# SH5_-_MICROCONTROLLER.net
KiCad netlist of a schematic drawn in Altium Designer
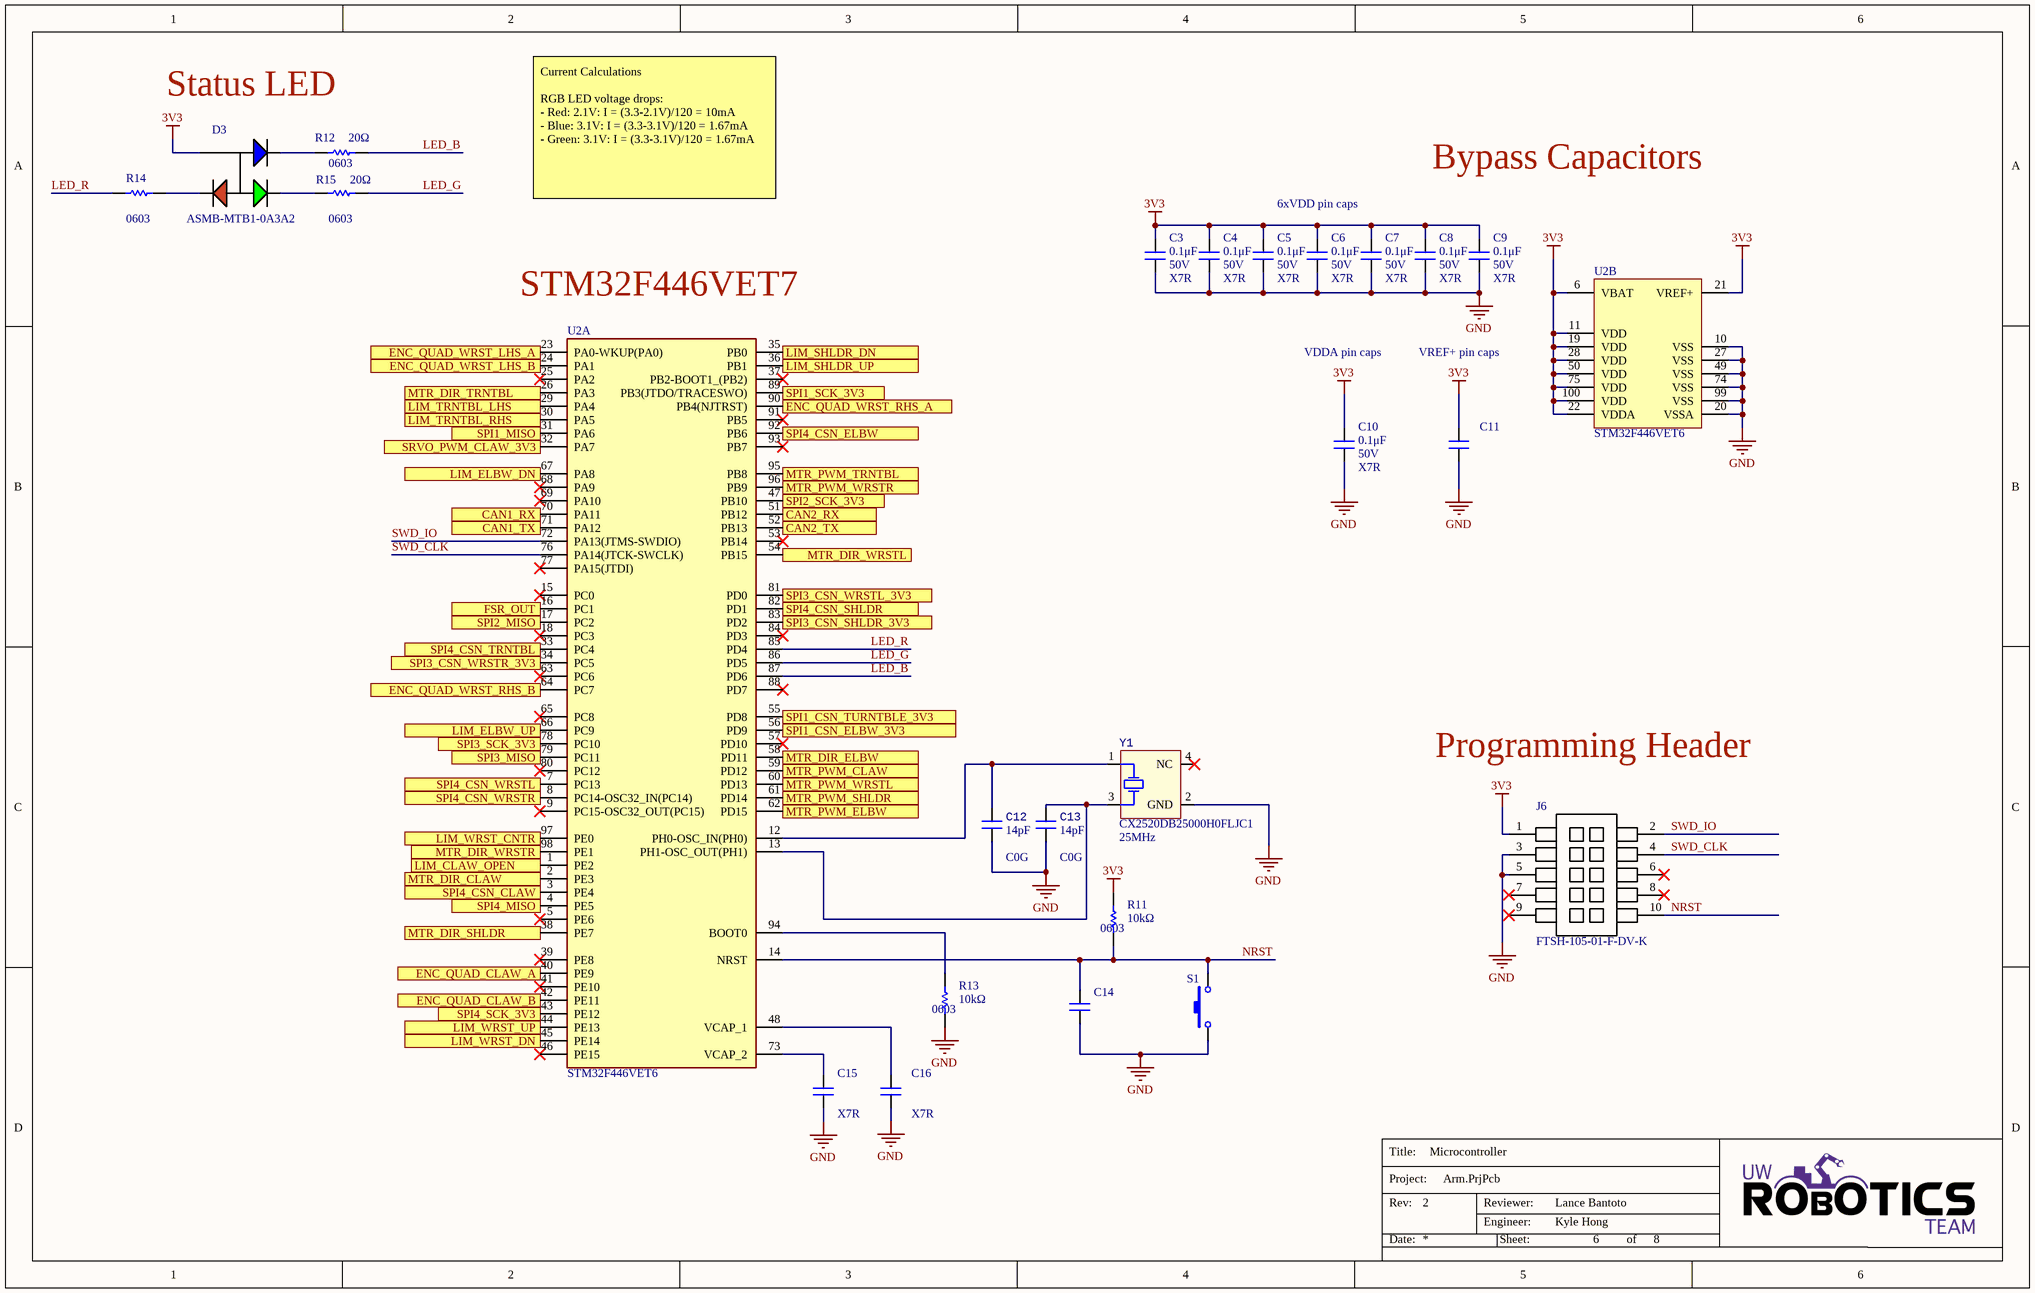
[diagram p0: SH5 - MICROCONTROLLER.SchDoc]

(export (version "E")
  (design (tool "Eeschema 10.0.6"))
  (components
    (comp (ref "C3")
      (value "0.1μF")
      (footprint "CAP0603")
      (description "CAP CER 0.1UF 50V X7R 0603")
      (fields
        (field (name "VOLTAGE RATING") "50V")
        (field (name "DIELECTRIC") "X7R")
        (field (name "Comment") "CAP_0.1uF_50V_0603")
      )
      (libsource (lib "UWRT_Schematic_Library_2020") (part "CAP_0.1uF_50V_0603"))
    )
    (comp (ref "C4")
      (value "0.1μF")
      (footprint "CAP0603")
      (description "CAP CER 0.1UF 50V X7R 0603")
      (fields
        (field (name "VOLTAGE RATING") "50V")
        (field (name "DIELECTRIC") "X7R")
        (field (name "Comment") "CAP_0.1uF_50V_0603")
      )
      (libsource (lib "UWRT_Schematic_Library_2020") (part "CAP_0.1uF_50V_0603"))
    )
    (comp (ref "C5")
      (value "0.1μF")
      (footprint "CAP0603")
      (description "CAP CER 0.1UF 50V X7R 0603")
      (fields
        (field (name "VOLTAGE RATING") "50V")
        (field (name "DIELECTRIC") "X7R")
        (field (name "Comment") "CAP_0.1uF_50V_0603")
      )
      (libsource (lib "UWRT_Schematic_Library_2020") (part "CAP_0.1uF_50V_0603"))
    )
    (comp (ref "C6")
      (value "0.1μF")
      (footprint "CAP0603")
      (description "CAP CER 0.1UF 50V X7R 0603")
      (fields
        (field (name "VOLTAGE RATING") "50V")
        (field (name "DIELECTRIC") "X7R")
        (field (name "Comment") "CAP_0.1uF_50V_0603")
      )
      (libsource (lib "UWRT_Schematic_Library_2020") (part "CAP_0.1uF_50V_0603"))
    )
    (comp (ref "C7")
      (value "0.1μF")
      (footprint "CAP0603")
      (description "CAP CER 0.1UF 50V X7R 0603")
      (fields
        (field (name "VOLTAGE RATING") "50V")
        (field (name "DIELECTRIC") "X7R")
        (field (name "Comment") "CAP_0.1uF_50V_0603")
      )
      (libsource (lib "UWRT_Schematic_Library_2020") (part "CAP_0.1uF_50V_0603"))
    )
    (comp (ref "C8")
      (value "0.1μF")
      (footprint "CAP0603")
      (description "CAP CER 0.1UF 50V X7R 0603")
      (fields
        (field (name "VOLTAGE RATING") "50V")
        (field (name "DIELECTRIC") "X7R")
        (field (name "Comment") "CAP_0.1uF_50V_0603")
      )
      (libsource (lib "UWRT_Schematic_Library_2020") (part "CAP_0.1uF_50V_0603"))
    )
    (comp (ref "C9")
      (value "0.1μF")
      (footprint "CAP0603")
      (description "CAP CER 0.1UF 50V X7R 0603")
      (fields
        (field (name "VOLTAGE RATING") "50V")
        (field (name "DIELECTRIC") "X7R")
        (field (name "Comment") "CAP_0.1uF_50V_0603")
      )
      (libsource (lib "UWRT_Schematic_Library_2020") (part "CAP_0.1uF_50V_0603"))
    )
    (comp (ref "C10")
      (value "0.1μF")
      (footprint "CAP0603")
      (description "CAP CER 0.1UF 50V X7R 0603")
      (fields
        (field (name "VOLTAGE RATING") "50V")
        (field (name "DIELECTRIC") "X7R")
        (field (name "Comment") "CAP_0.1uF_50V_0603")
      )
      (libsource (lib "UWRT_Schematic_Library_2020") (part "CAP_0.1uF_50V_0603"))
    )
    (comp (ref "C11")
      (value "CAP_1uF_25V_0603")
      (footprint "CAP0603")
      (description "CAP CER 1UF 25V X5R 0603")
      (libsource (lib "UWRT_Schematic_Library_2020") (part "CAP_1uF_25V_0603"))
    )
    (comp (ref "C12")
      (value "14pF")
      (footprint "CAP0603")
      (description "CAP CER 14PF 50V C0G/NP0 0603")
      (fields (field (name "DIELECTRIC") "C0G") (field (name "Comment") "CAP_14pF_50V_0603"))
      (libsource (lib "UWRT_Schematic_Library_2020") (part "CAP_14pF_50V_0603"))
    )
    (comp (ref "C13")
      (value "14pF")
      (footprint "CAP0603")
      (description "CAP CER 14PF 50V C0G/NP0 0603")
      (fields (field (name "DIELECTRIC") "C0G") (field (name "Comment") "CAP_14pF_50V_0603"))
      (libsource (lib "UWRT_Schematic_Library_2020") (part "CAP_14pF_50V_0603"))
    )
    (comp (ref "C14")
      (value "CAP_1uF_25V_0603")
      (footprint "CAP0603")
      (description "CAP CER 1UF 25V X5R 0603")
      (libsource (lib "UWRT_Schematic_Library_2020") (part "CAP_1uF_25V_0603"))
    )
    (comp (ref "C15")
      (value "CAP_4.7uF_50V_1206")
      (footprint "CAP1206")
      (description "CAP CER 4.7UF 50V X7R 1206")
      (fields (field (name "DIELECTRIC") "X7R"))
      (libsource (lib "UWRT_Schematic_Library_2020") (part "CAP_4.7uF_50V_1206"))
    )
    (comp (ref "C16")
      (value "CAP_4.7uF_50V_1206")
      (footprint "CAP1206")
      (description "CAP CER 4.7UF 50V X7R 1206")
      (fields (field (name "DIELECTRIC") "X7R"))
      (libsource (lib "UWRT_Schematic_Library_2020") (part "CAP_4.7uF_50V_1206"))
    )
    (comp (ref "D3")
      (value "LED_RGB")
      (footprint "LED_RGB")
      (description "LED RGB DIFFUSED 4PLCC SMD")
      (fields (field (name "MANUFACTURER PART NUMBER 1") "ASMB-MTB1-0A3A2"))
      (libsource (lib "UWRT_Schematic_Library_2020") (part "LED_RGB"))
    )
    (comp (ref "J6")
      (value "CON_PROGRAMMING")
      (footprint "FTSH-105-01-F-DV-K-P-TR")
      (description "CONN HEADER SMD 10POS 1.27MM")
      (fields (field (name "MANUFACTURER PART NUMBER 1") "FTSH-105-01-F-DV-K"))
      (libsource (lib "UWRT_Schematic_Library_2020") (part "CON_PROGRAMMING"))
    )
    (comp (ref "R11")
      (value "10kΩ")
      (footprint "RESC0603")
      (description "RES 10K OHM 5% 1/10W 0603")
      (fields (field (name "PACKAGE/FOOTPRINT") "0603") (field (name "Comment") "RES_10kΩ_0603_5%"))
      (libsource (lib "UWRT_Schematic_Library_2020") (part "RES_10kΩ_0603_5%"))
    )
    (comp (ref "R12")
      (value "20Ω")
      (footprint "RESC0603")
      (description "RES 20 OHM 5% 1/10W 0603")
      (fields (field (name "PACKAGE/FOOTPRINT") "0603") (field (name "Comment") "RES_20Ω_0603_5%"))
      (libsource (lib "UWRT_Schematic_Library_2020") (part "RES_20Ω_0603_5%"))
    )
    (comp (ref "R13")
      (value "10kΩ")
      (footprint "RESC0603")
      (description "RES 10K OHM 5% 1/10W 0603")
      (fields (field (name "PACKAGE/FOOTPRINT") "0603") (field (name "Comment") "RES_10kΩ_0603_5%"))
      (libsource (lib "UWRT_Schematic_Library_2020") (part "RES_10kΩ_0603_5%"))
    )
    (comp (ref "R14")
      (value "RES_120Ω_0603_5%_HP")
      (footprint "RESC0603")
      (description "RES 120 OHM 5% 1/4W 0603")
      (fields (field (name "PACKAGE/FOOTPRINT") "0603"))
      (libsource (lib "UWRT_Schematic_Library_2020") (part "RES_120Ω_0603_5%_HP"))
    )
    (comp (ref "R15")
      (value "20Ω")
      (footprint "RESC0603")
      (description "RES 20 OHM 5% 1/10W 0603")
      (fields (field (name "PACKAGE/FOOTPRINT") "0603") (field (name "Comment") "RES_20Ω_0603_5%"))
      (libsource (lib "UWRT_Schematic_Library_2020") (part "RES_20Ω_0603_5%"))
    )
    (comp (ref "S1")
      (value "SW_TACTILE")
      (footprint "B3U-1000P")
      (description "SWITCH TACTILE SPST-NO 0.05A 12V")
      (libsource (lib "UWRT_Schematic_Library_2020") (part "SW_TACTILE"))
    )
    (comp (ref "U2")
      (value "STM32F446VET6")
      (footprint "STM32F446VET6")
      (description "IC MCU 32BIT 512KB FLASH 100LQFP")
      (libsource (lib "UWRT_Schematic_Library_2020") (part "STM32F446VET6"))
    )
    (comp (ref "Y1")
      (value "CRYSTAL_25MHZ")
      (footprint "SOIC254P1016X440-4N")
      (description "CRYSTAL 25.0000MHZ 12PF SMD")
      (fields
        (field (name "MANUFACTURER PART NUMBER 1") "CX2520DB25000H0FLJC1")
        (field (name "FREQUENCY") "25MHz")
      )
      (libsource (lib "UWRT_Schematic_Library_2020") (part "CRYSTAL_25MHZ"))
    )
  )
  (nets
    (net (code "1") (name "/CAN1_RX") (class "Default")
      (node (ref "U2") (pin "70") (pinfunction "PA11_70") (pintype "passive"))
    )
    (net (code "2") (name "/CAN1_TX") (class "Default")
      (node (ref "U2") (pin "71") (pinfunction "PA12_71") (pintype "passive"))
    )
    (net (code "3") (name "/CAN2_RX") (class "Default")
      (node (ref "U2") (pin "51") (pinfunction "PB12_51") (pintype "passive"))
    )
    (net (code "4") (name "/CAN2_TX") (class "Default")
      (node (ref "U2") (pin "52") (pinfunction "PB13_52") (pintype "passive"))
    )
    (net (code "5") (name "/ENC_QUAD_CLAW_A") (class "Default")
      (node (ref "U2") (pin "40") (pinfunction "PE9_40") (pintype "passive"))
    )
    (net (code "6") (name "/ENC_QUAD_CLAW_B") (class "Default")
      (node (ref "U2") (pin "42") (pinfunction "PE11_42") (pintype "passive"))
    )
    (net (code "7") (name "/ENC_QUAD_WRST_LHS_A") (class "Default")
      (node (ref "U2") (pin "23") (pinfunction "PA0-WKUP(PA0)_23") (pintype "passive"))
    )
    (net (code "8") (name "/ENC_QUAD_WRST_LHS_B") (class "Default")
      (node (ref "U2") (pin "24") (pinfunction "PA1_24") (pintype "passive"))
    )
    (net (code "9") (name "/ENC_QUAD_WRST_RHS_A") (class "Default")
      (node (ref "U2") (pin "90") (pinfunction "PB4(NJTRST)_90") (pintype "passive"))
    )
    (net (code "10") (name "/ENC_QUAD_WRST_RHS_B") (class "Default")
      (node (ref "U2") (pin "64") (pinfunction "PC7_64") (pintype "passive"))
    )
    (net (code "11") (name "/FSR_OUT") (class "Default")
      (node (ref "U2") (pin "16") (pinfunction "PC1_16") (pintype "passive"))
    )
    (net (code "12") (name "/LED_B") (class "Default")
      (node (ref "R12") (pin "2") (pinfunction "2_2") (pintype "passive"))
      (node (ref "U2") (pin "87") (pinfunction "PD6_87") (pintype "passive"))
    )
    (net (code "13") (name "/LED_G") (class "Default")
      (node (ref "R15") (pin "2") (pinfunction "2_2") (pintype "passive"))
      (node (ref "U2") (pin "86") (pinfunction "PD5_86") (pintype "passive"))
    )
    (net (code "14") (name "/LED_R") (class "Default")
      (node (ref "R14") (pin "1") (pinfunction "1_1") (pintype "passive"))
      (node (ref "U2") (pin "85") (pinfunction "PD4_85") (pintype "passive"))
    )
    (net (code "15") (name "/LIM_CLAW_OPEN") (class "Default")
      (node (ref "U2") (pin "1") (pinfunction "PE2_1") (pintype "passive"))
    )
    (net (code "16") (name "/LIM_ELBW_DN") (class "Default")
      (node (ref "U2") (pin "67") (pinfunction "PA8_67") (pintype "passive"))
    )
    (net (code "17") (name "/LIM_ELBW_UP") (class "Default")
      (node (ref "U2") (pin "66") (pinfunction "PC9_66") (pintype "passive"))
    )
    (net (code "18") (name "/LIM_SHLDR_DN") (class "Default")
      (node (ref "U2") (pin "35") (pinfunction "PB0_35") (pintype "passive"))
    )
    (net (code "19") (name "/LIM_SHLDR_UP") (class "Default")
      (node (ref "U2") (pin "36") (pinfunction "PB1_36") (pintype "passive"))
    )
    (net (code "20") (name "/LIM_TRNTBL_LHS") (class "Default")
      (node (ref "U2") (pin "29") (pinfunction "PA4_29") (pintype "passive"))
    )
    (net (code "21") (name "/LIM_TRNTBL_RHS") (class "Default")
      (node (ref "U2") (pin "30") (pinfunction "PA5_30") (pintype "passive"))
    )
    (net (code "22") (name "/LIM_WRST_CNTR") (class "Default")
      (node (ref "U2") (pin "97") (pinfunction "PE0_97") (pintype "passive"))
    )
    (net (code "23") (name "/LIM_WRST_DN") (class "Default")
      (node (ref "U2") (pin "45") (pinfunction "PE14_45") (pintype "passive"))
    )
    (net (code "24") (name "/LIM_WRST_UP") (class "Default")
      (node (ref "U2") (pin "44") (pinfunction "PE13_44") (pintype "passive"))
    )
    (net (code "25") (name "/MTR_DIR_CLAW") (class "Default")
      (node (ref "U2") (pin "2") (pinfunction "PE3_2") (pintype "passive"))
    )
    (net (code "26") (name "/MTR_DIR_ELBW") (class "Default")
      (node (ref "U2") (pin "58") (pinfunction "PD11_58") (pintype "passive"))
    )
    (net (code "27") (name "/MTR_DIR_SHLDR") (class "Default")
      (node (ref "U2") (pin "38") (pinfunction "PE7_38") (pintype "passive"))
    )
    (net (code "28") (name "/MTR_DIR_TRNTBL") (class "Default")
      (node (ref "U2") (pin "26") (pinfunction "PA3_26") (pintype "passive"))
    )
    (net (code "29") (name "/MTR_DIR_WRSTL") (class "Default")
      (node (ref "U2") (pin "54") (pinfunction "PB15_54") (pintype "passive"))
    )
    (net (code "30") (name "/MTR_DIR_WRSTR") (class "Default")
      (node (ref "U2") (pin "98") (pinfunction "PE1_98") (pintype "passive"))
    )
    (net (code "31") (name "/MTR_PWM_CLAW") (class "Default")
      (node (ref "U2") (pin "59") (pinfunction "PD12_59") (pintype "passive"))
    )
    (net (code "32") (name "/MTR_PWM_ELBW") (class "Default")
      (node (ref "U2") (pin "62") (pinfunction "PD15_62") (pintype "passive"))
    )
    (net (code "33") (name "/MTR_PWM_SHLDR") (class "Default")
      (node (ref "U2") (pin "61") (pinfunction "PD14_61") (pintype "passive"))
    )
    (net (code "34") (name "/MTR_PWM_TRNTBL") (class "Default")
      (node (ref "U2") (pin "95") (pinfunction "PB8_95") (pintype "passive"))
    )
    (net (code "35") (name "/MTR_PWM_WRSTL") (class "Default")
      (node (ref "U2") (pin "60") (pinfunction "PD13_60") (pintype "passive"))
    )
    (net (code "36") (name "/MTR_PWM_WRSTR") (class "Default")
      (node (ref "U2") (pin "96") (pinfunction "PB9_96") (pintype "passive"))
    )
    (net (code "37") (name "/NRST") (class "Default")
      (node (ref "C14") (pin "2") (pinfunction "2_2") (pintype "passive"))
      (node (ref "J6") (pin "10") (pinfunction "10_10") (pintype "passive"))
      (node (ref "R11") (pin "2") (pinfunction "2_2") (pintype "passive"))
      (node (ref "S1") (pin "2") (pinfunction "2_2") (pintype "passive"))
      (node (ref "U2") (pin "14") (pinfunction "NRST_14") (pintype "passive"))
    )
    (net (code "38") (name "/SPI1_CSN_ELBW_3V3") (class "Default")
      (node (ref "U2") (pin "56") (pinfunction "PD9_56") (pintype "passive"))
    )
    (net (code "39") (name "/SPI1_CSN_TURNTBLE_3V3") (class "Default")
      (node (ref "U2") (pin "55") (pinfunction "PD8_55") (pintype "passive"))
    )
    (net (code "40") (name "/SPI1_MISO") (class "Default")
      (node (ref "U2") (pin "31") (pinfunction "PA6_31") (pintype "passive"))
    )
    (net (code "41") (name "/SPI1_SCK_3V3") (class "Default")
      (node (ref "U2") (pin "89") (pinfunction "PB3(JTDO/TRACESWO)_89") (pintype "passive"))
    )
    (net (code "42") (name "/SPI2_MISO") (class "Default")
      (node (ref "U2") (pin "17") (pinfunction "PC2_17") (pintype "passive"))
    )
    (net (code "43") (name "/SPI2_SCK_3V3") (class "Default")
      (node (ref "U2") (pin "47") (pinfunction "PB10_47") (pintype "passive"))
    )
    (net (code "44") (name "/SPI3_CSN_SHLDR_3V3") (class "Default")
      (node (ref "U2") (pin "83") (pinfunction "PD2_83") (pintype "passive"))
    )
    (net (code "45") (name "/SPI3_CSN_WRSTL_3V3") (class "Default")
      (node (ref "U2") (pin "81") (pinfunction "PD0_81") (pintype "passive"))
    )
    (net (code "46") (name "/SPI3_CSN_WRSTR_3V3") (class "Default")
      (node (ref "U2") (pin "34") (pinfunction "PC5_34") (pintype "passive"))
    )
    (net (code "47") (name "/SPI3_MISO") (class "Default")
      (node (ref "U2") (pin "79") (pinfunction "PC11_79") (pintype "passive"))
    )
    (net (code "48") (name "/SPI3_SCK_3V3") (class "Default")
      (node (ref "U2") (pin "78") (pinfunction "PC10_78") (pintype "passive"))
    )
    (net (code "49") (name "/SPI4_CSN_CLAW") (class "Default")
      (node (ref "U2") (pin "3") (pinfunction "PE4_3") (pintype "passive"))
    )
    (net (code "50") (name "/SPI4_CSN_ELBW") (class "Default")
      (node (ref "U2") (pin "92") (pinfunction "PB6_92") (pintype "passive"))
    )
    (net (code "51") (name "/SPI4_CSN_SHLDR") (class "Default")
      (node (ref "U2") (pin "82") (pinfunction "PD1_82") (pintype "passive"))
    )
    (net (code "52") (name "/SPI4_CSN_TRNTBL") (class "Default")
      (node (ref "U2") (pin "33") (pinfunction "PC4_33") (pintype "passive"))
    )
    (net (code "53") (name "/SPI4_CSN_WRSTL") (class "Default")
      (node (ref "U2") (pin "7") (pinfunction "PC13_7") (pintype "passive"))
    )
    (net (code "54") (name "/SPI4_CSN_WRSTR") (class "Default")
      (node (ref "U2") (pin "8") (pinfunction "PC14-OSC32_IN(PC14)_8") (pintype "passive"))
    )
    (net (code "55") (name "/SPI4_MISO") (class "Default")
      (node (ref "U2") (pin "4") (pinfunction "PE5_4") (pintype "passive"))
    )
    (net (code "56") (name "/SPI4_SCK_3V3") (class "Default")
      (node (ref "U2") (pin "43") (pinfunction "PE12_43") (pintype "passive"))
    )
    (net (code "57") (name "/SRVO_PWM_CLAW_3V3") (class "Default")
      (node (ref "U2") (pin "32") (pinfunction "PA7_32") (pintype "passive"))
    )
    (net (code "58") (name "/SWD_CLK") (class "Default")
      (node (ref "J6") (pin "4") (pinfunction "4_4") (pintype "passive"))
      (node (ref "U2") (pin "76") (pinfunction "PA14(JTCK-SWCLK)_76") (pintype "passive"))
    )
    (net (code "59") (name "/SWD_IO") (class "Default")
      (node (ref "J6") (pin "2") (pinfunction "2_2") (pintype "passive"))
      (node (ref "U2") (pin "72") (pinfunction "PA13(JTMS-SWDIO)_72") (pintype "passive"))
    )
    (net (code "60") (name "3V3") (class "Default")
      (node (ref "C10") (pin "2") (pinfunction "2_2") (pintype "passive"))
      (node (ref "C11") (pin "2") (pinfunction "2_2") (pintype "passive"))
      (node (ref "C3") (pin "1") (pinfunction "1_1") (pintype "passive"))
      (node (ref "C4") (pin "1") (pinfunction "1_1") (pintype "passive"))
      (node (ref "C5") (pin "1") (pinfunction "1_1") (pintype "passive"))
      (node (ref "C6") (pin "1") (pinfunction "1_1") (pintype "passive"))
      (node (ref "C7") (pin "1") (pinfunction "1_1") (pintype "passive"))
      (node (ref "C8") (pin "1") (pinfunction "1_1") (pintype "passive"))
      (node (ref "C9") (pin "1") (pinfunction "1_1") (pintype "passive"))
      (node (ref "D3") (pin "4") (pinfunction "COMMON_ANODE_4") (pintype "passive"))
      (node (ref "J6") (pin "1") (pinfunction "1_1") (pintype "passive"))
      (node (ref "R11") (pin "1") (pinfunction "1_1") (pintype "passive"))
      (node (ref "U2") (pin "100") (pinfunction "VDD_100") (pintype "passive"))
      (node (ref "U2") (pin "11") (pinfunction "VDD_11") (pintype "passive"))
      (node (ref "U2") (pin "19") (pinfunction "VDD_19") (pintype "passive"))
      (node (ref "U2") (pin "21") (pinfunction "VREF+_21") (pintype "passive"))
      (node (ref "U2") (pin "22") (pinfunction "VDDA_22") (pintype "passive"))
      (node (ref "U2") (pin "28") (pinfunction "VDD_28") (pintype "passive"))
      (node (ref "U2") (pin "50") (pinfunction "VDD_50") (pintype "passive"))
      (node (ref "U2") (pin "6") (pinfunction "VBAT_6") (pintype "passive"))
      (node (ref "U2") (pin "75") (pinfunction "VDD_75") (pintype "passive"))
    )
    (net (code "61") (name "GND") (class "Default")
      (node (ref "C10") (pin "1") (pinfunction "1_1") (pintype "passive"))
      (node (ref "C11") (pin "1") (pinfunction "1_1") (pintype "passive"))
      (node (ref "C12") (pin "1") (pinfunction "1_1") (pintype "passive"))
      (node (ref "C13") (pin "1") (pinfunction "1_1") (pintype "passive"))
      (node (ref "C14") (pin "1") (pinfunction "1_1") (pintype "passive"))
      (node (ref "C15") (pin "1") (pinfunction "1_1") (pintype "passive"))
      (node (ref "C16") (pin "1") (pinfunction "1_1") (pintype "passive"))
      (node (ref "C3") (pin "2") (pinfunction "2_2") (pintype "passive"))
      (node (ref "C4") (pin "2") (pinfunction "2_2") (pintype "passive"))
      (node (ref "C5") (pin "2") (pinfunction "2_2") (pintype "passive"))
      (node (ref "C6") (pin "2") (pinfunction "2_2") (pintype "passive"))
      (node (ref "C7") (pin "2") (pinfunction "2_2") (pintype "passive"))
      (node (ref "C8") (pin "2") (pinfunction "2_2") (pintype "passive"))
      (node (ref "C9") (pin "2") (pinfunction "2_2") (pintype "passive"))
      (node (ref "J6") (pin "3") (pinfunction "3_3") (pintype "passive"))
      (node (ref "J6") (pin "5") (pinfunction "5_5") (pintype "passive"))
      (node (ref "R13") (pin "2") (pinfunction "2_2") (pintype "passive"))
      (node (ref "S1") (pin "1") (pinfunction "1_1") (pintype "passive"))
      (node (ref "U2") (pin "10") (pinfunction "VSS_10") (pintype "passive"))
      (node (ref "U2") (pin "20") (pinfunction "VSSA_20") (pintype "passive"))
      (node (ref "U2") (pin "27") (pinfunction "VSS_27") (pintype "passive"))
      (node (ref "U2") (pin "49") (pinfunction "VSS_49") (pintype "passive"))
      (node (ref "U2") (pin "74") (pinfunction "VSS_74") (pintype "passive"))
      (node (ref "U2") (pin "99") (pinfunction "VSS_99") (pintype "passive"))
      (node (ref "Y1") (pin "2") (pinfunction "GND_2") (pintype "power_in"))
    )
    (net (code "62") (name "Net-(D3-CATHODE_(BLUE))") (class "Default")
      (node (ref "D3") (pin "3") (pinfunction "CATHODE_(BLUE)_3") (pintype "passive"))
      (node (ref "R12") (pin "1") (pinfunction "1_1") (pintype "passive"))
    )
    (net (code "63") (name "Net-(D3-CATHODE_(GREEN))") (class "Default")
      (node (ref "D3") (pin "2") (pinfunction "CATHODE_(GREEN)_2") (pintype "passive"))
      (node (ref "R15") (pin "1") (pinfunction "1_1") (pintype "passive"))
    )
    (net (code "64") (name "Net-(D3-CATHODE_(RED))") (class "Default")
      (node (ref "D3") (pin "1") (pinfunction "CATHODE_(RED)_1") (pintype "passive"))
      (node (ref "R14") (pin "2") (pinfunction "2_2") (pintype "passive"))
    )
    (net (code "65") (name "Net-(U2A-BOOT0)") (class "Default")
      (node (ref "R13") (pin "1") (pinfunction "1_1") (pintype "passive"))
      (node (ref "U2") (pin "94") (pinfunction "BOOT0_94") (pintype "passive"))
    )
    (net (code "66") (name "Net-(U2A-PH0-OSC_IN(PH0))") (class "Default")
      (node (ref "C12") (pin "2") (pinfunction "2_2") (pintype "passive"))
      (node (ref "U2") (pin "12") (pinfunction "PH0-OSC_IN(PH0)_12") (pintype "passive"))
      (node (ref "Y1") (pin "1") (pinfunction "HOT_1") (pintype "passive"))
    )
    (net (code "67") (name "Net-(U2A-PH1-OSC_OUT(PH1))") (class "Default")
      (node (ref "C13") (pin "2") (pinfunction "2_2") (pintype "passive"))
      (node (ref "U2") (pin "13") (pinfunction "PH1-OSC_OUT(PH1)_13") (pintype "passive"))
      (node (ref "Y1") (pin "3") (pinfunction "HOT_3") (pintype "passive"))
    )
    (net (code "68") (name "Net-(U2A-VCAP_1)") (class "Default")
      (node (ref "C16") (pin "2") (pinfunction "2_2") (pintype "passive"))
      (node (ref "U2") (pin "48") (pinfunction "VCAP_1_48") (pintype "passive"))
    )
    (net (code "69") (name "Net-(U2A-VCAP_2)") (class "Default")
      (node (ref "C15") (pin "2") (pinfunction "2_2") (pintype "passive"))
      (node (ref "U2") (pin "73") (pinfunction "VCAP_2_73") (pintype "passive"))
    )
    (net (code "70") (name "unconnected-(J6-Pad6)") (class "Default")
      (node (ref "J6") (pin "6") (pinfunction "6_6") (pintype "passive+no_connect"))
    )
    (net (code "71") (name "unconnected-(J6-Pad7)") (class "Default")
      (node (ref "J6") (pin "7") (pinfunction "7_7") (pintype "passive+no_connect"))
    )
    (net (code "72") (name "unconnected-(J6-Pad8)") (class "Default")
      (node (ref "J6") (pin "8") (pinfunction "8_8") (pintype "passive+no_connect"))
    )
    (net (code "73") (name "unconnected-(J6-Pad9)") (class "Default")
      (node (ref "J6") (pin "9") (pinfunction "9_9") (pintype "passive+no_connect"))
    )
    (net (code "74") (name "unconnected-(U2A-PA2-Pad25)") (class "Default")
      (node (ref "U2") (pin "25") (pinfunction "PA2_25") (pintype "passive+no_connect"))
    )
    (net (code "75") (name "unconnected-(U2A-PA9-Pad68)") (class "Default")
      (node (ref "U2") (pin "68") (pinfunction "PA9_68") (pintype "passive+no_connect"))
    )
    (net (code "76") (name "unconnected-(U2A-PA10-Pad69)") (class "Default")
      (node (ref "U2") (pin "69") (pinfunction "PA10_69") (pintype "passive+no_connect"))
    )
    (net (code "77") (name "unconnected-(U2A-PA15(JTDI)-Pad77)") (class "Default")
      (node (ref "U2") (pin "77") (pinfunction "PA15(JTDI)_77") (pintype "passive+no_connect"))
    )
    (net (code "78") (name "unconnected-(U2A-PB2-BOOT1_(PB2)-Pad37)") (class "Default")
      (node (ref "U2") (pin "37") (pinfunction "PB2-BOOT1_(PB2)_37") (pintype "passive+no_connect"))
    )
    (net (code "79") (name "unconnected-(U2A-PB5-Pad91)") (class "Default")
      (node (ref "U2") (pin "91") (pinfunction "PB5_91") (pintype "passive+no_connect"))
    )
    (net (code "80") (name "unconnected-(U2A-PB7-Pad93)") (class "Default")
      (node (ref "U2") (pin "93") (pinfunction "PB7_93") (pintype "passive+no_connect"))
    )
    (net (code "81") (name "unconnected-(U2A-PB14-Pad53)") (class "Default")
      (node (ref "U2") (pin "53") (pinfunction "PB14_53") (pintype "passive+no_connect"))
    )
    (net (code "82") (name "unconnected-(U2A-PC0-Pad15)") (class "Default")
      (node (ref "U2") (pin "15") (pinfunction "PC0_15") (pintype "passive+no_connect"))
    )
    (net (code "83") (name "unconnected-(U2A-PC3-Pad18)") (class "Default")
      (node (ref "U2") (pin "18") (pinfunction "PC3_18") (pintype "passive+no_connect"))
    )
    (net (code "84") (name "unconnected-(U2A-PC6-Pad63)") (class "Default")
      (node (ref "U2") (pin "63") (pinfunction "PC6_63") (pintype "passive+no_connect"))
    )
    (net (code "85") (name "unconnected-(U2A-PC8-Pad65)") (class "Default")
      (node (ref "U2") (pin "65") (pinfunction "PC8_65") (pintype "passive+no_connect"))
    )
    (net (code "86") (name "unconnected-(U2A-PC12-Pad80)") (class "Default")
      (node (ref "U2") (pin "80") (pinfunction "PC12_80") (pintype "passive+no_connect"))
    )
    (net (code "87") (name "unconnected-(U2A-PC15-OSC32_OUT(PC15)-Pad9)") (class "Default")
      (node (ref "U2") (pin "9") (pinfunction "PC15-OSC32_OUT(PC15)_9") (pintype "passive+no_connect"))
    )
    (net (code "88") (name "unconnected-(U2A-PD3-Pad84)") (class "Default")
      (node (ref "U2") (pin "84") (pinfunction "PD3_84") (pintype "passive+no_connect"))
    )
    (net (code "89") (name "unconnected-(U2A-PD7-Pad88)") (class "Default")
      (node (ref "U2") (pin "88") (pinfunction "PD7_88") (pintype "passive+no_connect"))
    )
    (net (code "90") (name "unconnected-(U2A-PD10-Pad57)") (class "Default")
      (node (ref "U2") (pin "57") (pinfunction "PD10_57") (pintype "passive+no_connect"))
    )
    (net (code "91") (name "unconnected-(U2A-PE6-Pad5)") (class "Default")
      (node (ref "U2") (pin "5") (pinfunction "PE6_5") (pintype "passive+no_connect"))
    )
    (net (code "92") (name "unconnected-(U2A-PE8-Pad39)") (class "Default")
      (node (ref "U2") (pin "39") (pinfunction "PE8_39") (pintype "passive+no_connect"))
    )
    (net (code "93") (name "unconnected-(U2A-PE10-Pad41)") (class "Default")
      (node (ref "U2") (pin "41") (pinfunction "PE10_41") (pintype "passive+no_connect"))
    )
    (net (code "94") (name "unconnected-(U2A-PE15-Pad46)") (class "Default")
      (node (ref "U2") (pin "46") (pinfunction "PE15_46") (pintype "passive+no_connect"))
    )
    (net (code "95") (name "unconnected-(Y1-NC-Pad4)") (class "Default")
      (node (ref "Y1") (pin "4") (pinfunction "NC_4") (pintype "passive+no_connect"))
    )
  )
)
